# 03_ICs.net
KiCad netlist of a schematic drawn in Altium Designer
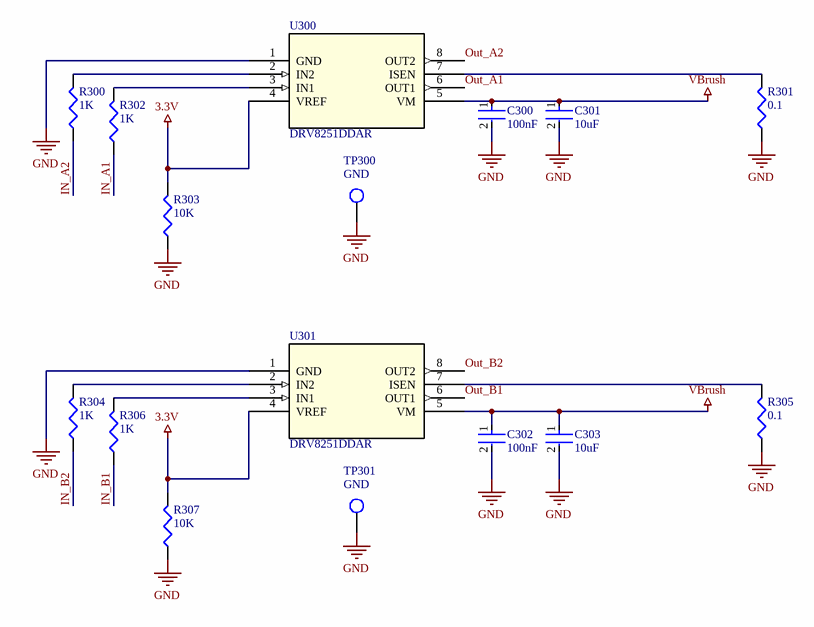
[diagram p0: 03_ICs.SchDoc]

(export (version "E")
  (design (tool "Eeschema 10.0.6"))
  (components
    (comp (ref "C300")
      (value "100nF")
      (footprint "CAP_0805")
      (description "CAP CER 0.1UF 50V X7R 0805")
      (fields
        (field (name "MANUFACTURER") "KEMET")
        (field (name "MANUFACTURER PART NUMBER") "C0805C104K5RACTU")
      )
      (libsource (lib "ECE453") (part "CMP-2007-00279-2"))
    )
    (comp (ref "C301")
      (value "10uF")
      (footprint "CAP_0805")
      (description "CAP CER 10UF 10V X5R 0805")
      (fields
        (field (name "MANUFACTURER") "KEMET")
        (field (name "MANUFACTURER PART NUMBER") "C0805C106K8PACTU")
      )
      (libsource (lib "ECE453") (part "CMP-2007-03243-2"))
    )
    (comp (ref "C302")
      (value "100nF")
      (footprint "CAP_0805")
      (description "CAP CER 0.1UF 50V X7R 0805")
      (fields
        (field (name "MANUFACTURER") "KEMET")
        (field (name "MANUFACTURER PART NUMBER") "C0805C104K5RACTU")
      )
      (libsource (lib "ECE453") (part "CMP-2007-00279-2"))
    )
    (comp (ref "C303")
      (value "10uF")
      (footprint "CAP_0805")
      (description "CAP CER 10UF 10V X5R 0805")
      (fields
        (field (name "MANUFACTURER") "KEMET")
        (field (name "MANUFACTURER PART NUMBER") "C0805C106K8PACTU")
      )
      (libsource (lib "ECE453") (part "CMP-2007-03243-2"))
    )
    (comp (ref "R300")
      (value "1K")
      (footprint "RESC2013X70X40ML20T20")
      (description "Res Thick Film 0805 1K Ohm 1% 0.125W(1/8W) ±100ppm/C Pad SMD Automotive T/R")
      (fields
        (field (name "MANUFACTURER") "Stackpole Electronics")
        (field (name "MANUFACTURER PART NUMBER") "RMCF0805FT1K00")
      )
      (libsource (lib "ECE453") (part "Res3_1"))
    )
    (comp (ref "R301")
      (value "0.1")
      (footprint "RESC2013X70X40ML20T20")
      (description "Res 0.1 Ohm 1% 1W 1206")
      (fields
        (field (name "MANUFACTURER") "Cyntec")
        (field (name "MANUFACTURER PART NUMBER") "SCRR1206S1-R100F")
      )
      (libsource (lib "ECE453") (part "Res3_2"))
    )
    (comp (ref "R302")
      (value "1K")
      (footprint "RESC2013X70X40ML20T20")
      (description "Res Thick Film 0805 1K Ohm 1% 0.125W(1/8W) ±100ppm/C Pad SMD Automotive T/R")
      (fields
        (field (name "MANUFACTURER") "Stackpole Electronics")
        (field (name "MANUFACTURER PART NUMBER") "RMCF0805FT1K00")
      )
      (libsource (lib "ECE453") (part "Res3_1"))
    )
    (comp (ref "R303")
      (value "10K")
      (footprint "RESC2013X70X40ML20T20")
      (description "Res Thick Film 0805 10K Ohm 1% 0.125W ±100ppm/°C Molded SMD Paper T/R")
      (fields
        (field (name "MANUFACTURER") "Stackpole Electronics")
        (field (name "MANUFACTURER PART NUMBER") "RMCF0805FT10K0")
      )
      (libsource (lib "ECE453") (part "Res3"))
    )
    (comp (ref "R304")
      (value "1K")
      (footprint "RESC2013X70X40ML20T20")
      (description "Res Thick Film 0805 1K Ohm 1% 0.125W(1/8W) ±100ppm/C Pad SMD Automotive T/R")
      (fields
        (field (name "MANUFACTURER") "Stackpole Electronics")
        (field (name "MANUFACTURER PART NUMBER") "RMCF0805FT1K00")
      )
      (libsource (lib "ECE453") (part "Res3_1"))
    )
    (comp (ref "R305")
      (value "0.1")
      (footprint "RESC2013X70X40ML20T20")
      (description "Res 0.1 Ohm 1% 1W 1206")
      (fields
        (field (name "MANUFACTURER") "Cyntec")
        (field (name "MANUFACTURER PART NUMBER") "SCRR1206S1-R100F")
      )
      (libsource (lib "ECE453") (part "Res3_2"))
    )
    (comp (ref "R306")
      (value "1K")
      (footprint "RESC2013X70X40ML20T20")
      (description "Res Thick Film 0805 1K Ohm 1% 0.125W(1/8W) ±100ppm/C Pad SMD Automotive T/R")
      (fields
        (field (name "MANUFACTURER") "Stackpole Electronics")
        (field (name "MANUFACTURER PART NUMBER") "RMCF0805FT1K00")
      )
      (libsource (lib "ECE453") (part "Res3_1"))
    )
    (comp (ref "R307")
      (value "10K")
      (footprint "RESC2013X70X40ML20T20")
      (description "Res Thick Film 0805 10K Ohm 1% 0.125W ±100ppm/°C Molded SMD Paper T/R")
      (fields
        (field (name "MANUFACTURER") "Stackpole Electronics")
        (field (name "MANUFACTURER PART NUMBER") "RMCF0805FT10K0")
      )
      (libsource (lib "ECE453") (part "Res3"))
    )
    (comp (ref "TP300")
      (value "GND")
      (footprint "TP-SMC-1206")
      (description "Test Point SMD 1206")
      (fields
        (field (name "MANUFACTURER") "TE Connectivity (Tyco Electronics)")
        (field (name "MANUFACTURER PART NUMBER") "1625854-1")
      )
      (libsource (lib "ECE453") (part "TP_1206"))
    )
    (comp (ref "TP301")
      (value "GND")
      (footprint "TP-SMC-1206")
      (description "Test Point SMD 1206")
      (fields
        (field (name "MANUFACTURER") "TE Connectivity (Tyco Electronics)")
        (field (name "MANUFACTURER PART NUMBER") "1625854-1")
      )
      (libsource (lib "ECE453") (part "TP_1206"))
    )
    (comp (ref "U300")
      (value "DRV8251DDAR")
      (footprint "POWERPAD_DDA_TEX-M")
      (description "No Description Available")
      (fields (field (name "COPYRIGHT") "Copyright (C) 2023 Ultra Librarian. All rights reserved."))
      (libsource (lib "DRV8251DDAR") (part "DRV8251DDAR"))
    )
    (comp (ref "U301")
      (value "DRV8251DDAR")
      (footprint "POWERPAD_DDA_TEX-M")
      (description "No Description Available")
      (fields (field (name "COPYRIGHT") "Copyright (C) 2023 Ultra Librarian. All rights reserved."))
      (libsource (lib "DRV8251DDAR") (part "DRV8251DDAR"))
    )
  )
  (nets
    (net (code "1") (name "/IN_A1") (class "Default")
      (node (ref "R302") (pin "1") (pinfunction "1_1") (pintype "passive"))
    )
    (net (code "2") (name "/IN_A2") (class "Default")
      (node (ref "R300") (pin "1") (pinfunction "1_1") (pintype "passive"))
    )
    (net (code "3") (name "/IN_B1") (class "Default")
      (node (ref "R306") (pin "1") (pinfunction "1_1") (pintype "passive"))
    )
    (net (code "4") (name "/IN_B2") (class "Default")
      (node (ref "R304") (pin "1") (pinfunction "1_1") (pintype "passive"))
    )
    (net (code "5") (name "/Out_A1") (class "Default")
      (node (ref "U300") (pin "6") (pinfunction "OUT1_6") (pintype "output"))
    )
    (net (code "6") (name "/Out_A2") (class "Default")
      (node (ref "U300") (pin "8") (pinfunction "OUT2_8") (pintype "output"))
    )
    (net (code "7") (name "/Out_B1") (class "Default")
      (node (ref "U301") (pin "6") (pinfunction "OUT1_6") (pintype "output"))
    )
    (net (code "8") (name "/Out_B2") (class "Default")
      (node (ref "U301") (pin "8") (pinfunction "OUT2_8") (pintype "output"))
    )
    (net (code "9") (name "3.3V") (class "Default")
      (node (ref "R303") (pin "2") (pinfunction "2_2") (pintype "passive"))
      (node (ref "R307") (pin "2") (pinfunction "2_2") (pintype "passive"))
      (node (ref "U300") (pin "4") (pinfunction "VREF_4") (pintype "power_in"))
      (node (ref "U301") (pin "4") (pinfunction "VREF_4") (pintype "power_in"))
    )
    (net (code "10") (name "GND") (class "Default")
      (node (ref "C300") (pin "2") (pinfunction "2_2") (pintype "passive"))
      (node (ref "C301") (pin "2") (pinfunction "2_2") (pintype "passive"))
      (node (ref "C302") (pin "2") (pinfunction "2_2") (pintype "passive"))
      (node (ref "C303") (pin "2") (pinfunction "2_2") (pintype "passive"))
      (node (ref "R301") (pin "1") (pinfunction "1_1") (pintype "passive"))
      (node (ref "R303") (pin "1") (pinfunction "1_1") (pintype "passive"))
      (node (ref "R305") (pin "1") (pinfunction "1_1") (pintype "passive"))
      (node (ref "R307") (pin "1") (pinfunction "1_1") (pintype "passive"))
      (node (ref "TP300") (pin "1") (pintype "passive"))
      (node (ref "TP301") (pin "1") (pintype "passive"))
      (node (ref "U300") (pin "1") (pinfunction "GND_1") (pintype "power_in"))
      (node (ref "U301") (pin "1") (pinfunction "GND_1") (pintype "power_in"))
    )
    (net (code "11") (name "Net-(U300-IN1)") (class "Default")
      (node (ref "R302") (pin "2") (pinfunction "2_2") (pintype "passive"))
      (node (ref "U300") (pin "3") (pinfunction "IN1_3") (pintype "input"))
    )
    (net (code "12") (name "Net-(U300-IN2)") (class "Default")
      (node (ref "R300") (pin "2") (pinfunction "2_2") (pintype "passive"))
      (node (ref "U300") (pin "2") (pinfunction "IN2_2") (pintype "input"))
    )
    (net (code "13") (name "Net-(U300-ISEN)") (class "Default")
      (node (ref "R301") (pin "2") (pinfunction "2_2") (pintype "passive"))
      (node (ref "U300") (pin "7") (pinfunction "ISEN_7") (pintype "power_in"))
    )
    (net (code "14") (name "Net-(U301-IN1)") (class "Default")
      (node (ref "R306") (pin "2") (pinfunction "2_2") (pintype "passive"))
      (node (ref "U301") (pin "3") (pinfunction "IN1_3") (pintype "input"))
    )
    (net (code "15") (name "Net-(U301-IN2)") (class "Default")
      (node (ref "R304") (pin "2") (pinfunction "2_2") (pintype "passive"))
      (node (ref "U301") (pin "2") (pinfunction "IN2_2") (pintype "input"))
    )
    (net (code "16") (name "Net-(U301-ISEN)") (class "Default")
      (node (ref "R305") (pin "2") (pinfunction "2_2") (pintype "passive"))
      (node (ref "U301") (pin "7") (pinfunction "ISEN_7") (pintype "power_in"))
    )
    (net (code "17") (name "VBrush") (class "Default")
      (node (ref "C300") (pin "1") (pinfunction "1_1") (pintype "passive"))
      (node (ref "C301") (pin "1") (pinfunction "1_1") (pintype "passive"))
      (node (ref "C302") (pin "1") (pinfunction "1_1") (pintype "passive"))
      (node (ref "C303") (pin "1") (pinfunction "1_1") (pintype "passive"))
      (node (ref "U300") (pin "5") (pinfunction "VM_5") (pintype "power_in"))
      (node (ref "U301") (pin "5") (pinfunction "VM_5") (pintype "power_in"))
    )
  )
)
